# Buttons.net
KiCad netlist of a schematic drawn in Altium Designer
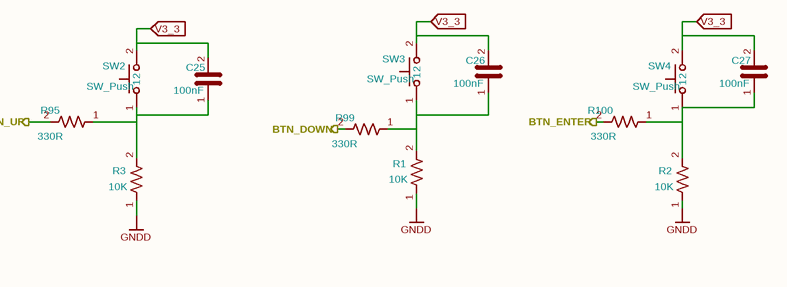
[diagram p0: Buttons.SchDoc]

(export (version "E")
  (design (tool "Eeschema 10.0.6"))
  (components
    (comp (ref "C25")
      (value "100nF")
      (footprint "C_0603_1608Metric")
      (description "X7R 100nF 50V ±10% 0603 Multilayer Ceramic")
      (fields (field (name "MP") "CC0603KRX7R9BB104") (field (name "MF") "YAGEO"))
      (libsource (lib "*") (part "C_3"))
    )
    (comp (ref "C26")
      (value "100nF")
      (footprint "C_0603_1608Metric")
      (description "X7R 100nF 50V ±10% 0603 Multilayer Ceramic")
      (fields (field (name "MP") "CC0603KRX7R9BB104") (field (name "MF") "YAGEO"))
      (libsource (lib "*") (part "C_3"))
    )
    (comp (ref "C27")
      (value "100nF")
      (footprint "C_0603_1608Metric")
      (description "X7R 100nF 50V ±10% 0603 Multilayer Ceramic")
      (fields (field (name "MP") "CC0603KRX7R9BB104") (field (name "MF") "YAGEO"))
      (libsource (lib "*") (part "C_3"))
    )
    (comp (ref "R1")
      (value "10K")
      (footprint "R_0603_1608Metric")
      (description "100mW Thick Film Resistors 75V ±100ppm/℃ ±5% 10kΩ 0603 Chip Resistor - Surface Mount ROHS")
      (fields (field (name "MP") "FRC0603J103TS") (field (name "MF") "FOJAN"))
      (libsource (lib "Device") (part "R_US"))
    )
    (comp (ref "R2")
      (value "10K")
      (footprint "R_0603_1608Metric")
      (description "100mW Thick Film Resistors 75V ±100ppm/℃ ±5% 10kΩ 0603 Chip Resistor - Surface Mount ROHS")
      (fields (field (name "MP") "FRC0603J103TS") (field (name "MF") "FOJAN"))
      (libsource (lib "Device") (part "R_US"))
    )
    (comp (ref "R3")
      (value "10K")
      (footprint "R_0603_1608Metric")
      (description "100mW Thick Film Resistors 75V ±100ppm/℃ ±5% 10kΩ 0603 Chip Resistor - Surface Mount ROHS")
      (fields (field (name "MP") "FRC0603J103TS") (field (name "MF") "FOJAN"))
      (libsource (lib "Device") (part "R_US"))
    )
    (comp (ref "R95")
      (value "330R")
      (footprint "R_0603_1608Metric")
      (description "RES 330Ω ±5% 100mW 0603")
      (fields (field (name "MP") "FRC0603J331 TS") (field (name "MF") "FOJAN"))
      (libsource (lib "Device") (part "R_US"))
    )
    (comp (ref "R99")
      (value "330R")
      (footprint "R_0603_1608Metric")
      (description "RES 330Ω ±5% 100mW 0603")
      (fields (field (name "MP") "FRC0603J331 TS") (field (name "MF") "FOJAN"))
      (libsource (lib "Device") (part "R_US"))
    )
    (comp (ref "R100")
      (value "330R")
      (footprint "R_0603_1608Metric")
      (description "RES 330Ω ±5% 100mW 0603")
      (fields (field (name "MP") "FRC0603J331 TS") (field (name "MF") "FOJAN"))
      (libsource (lib "Device") (part "R_US"))
    )
    (comp (ref "SW2")
      (value "SW_Push")
      (footprint "SW_SPST_Omron_B3FS-100xP")
      (description "Height 8mm SMD,12x12mm Tactile Switches RoHS")
      (fields (field (name "MP") "KH-12X12X8H-SMT") (field (name "MF") "kinghelm"))
      (libsource (lib "Switch") (part "SW_Push"))
    )
    (comp (ref "SW3")
      (value "SW_Push")
      (footprint "SW_SPST_Omron_B3FS-100xP")
      (description "Height 8mm SMD,12x12mm Tactile Switches RoHS")
      (fields (field (name "MP") "KH-12X12X8H-SMT") (field (name "MF") "kinghelm"))
      (libsource (lib "Switch") (part "SW_Push"))
    )
    (comp (ref "SW4")
      (value "SW_Push")
      (footprint "SW_SPST_Omron_B3FS-100xP")
      (description "Height 8mm SMD,12x12mm Tactile Switches RoHS")
      (fields (field (name "MP") "KH-12X12X8H-SMT") (field (name "MF") "kinghelm"))
      (libsource (lib "Switch") (part "SW_Push"))
    )
  )
  (nets
    (net (code "1") (name "/BTN_DOWN") (class "Default")
      (node (ref "R99") (pin "2") (pinfunction "2_2") (pintype "passive"))
    )
    (net (code "2") (name "/BTN_ENTER") (class "Default")
      (node (ref "R100") (pin "2") (pinfunction "2_2") (pintype "passive"))
    )
    (net (code "3") (name "/BTN_UP") (class "Default")
      (node (ref "R95") (pin "2") (pinfunction "2_2") (pintype "passive"))
    )
    (net (code "4") (name "/V3_3") (class "Default")
      (node (ref "C25") (pin "2") (pinfunction "2_2") (pintype "passive"))
      (node (ref "C26") (pin "2") (pinfunction "2_2") (pintype "passive"))
      (node (ref "C27") (pin "2") (pinfunction "2_2") (pintype "passive"))
      (node (ref "SW2") (pin "2") (pinfunction "2_2") (pintype "passive"))
      (node (ref "SW3") (pin "2") (pinfunction "2_2") (pintype "passive"))
      (node (ref "SW4") (pin "2") (pinfunction "2_2") (pintype "passive"))
    )
    (net (code "5") (name "GNDD") (class "Default")
      (node (ref "R1") (pin "1") (pinfunction "1_1") (pintype "passive"))
      (node (ref "R2") (pin "1") (pinfunction "1_1") (pintype "passive"))
      (node (ref "R3") (pin "1") (pinfunction "1_1") (pintype "passive"))
    )
    (net (code "6") (name "Net-(C25-Pad1)") (class "Default")
      (node (ref "C25") (pin "1") (pinfunction "1_1") (pintype "passive"))
      (node (ref "R3") (pin "2") (pinfunction "2_2") (pintype "passive"))
      (node (ref "R95") (pin "1") (pinfunction "1_1") (pintype "passive"))
      (node (ref "SW2") (pin "1") (pinfunction "1_1") (pintype "passive"))
    )
    (net (code "7") (name "Net-(C26-Pad1)") (class "Default")
      (node (ref "C26") (pin "1") (pinfunction "1_1") (pintype "passive"))
      (node (ref "R1") (pin "2") (pinfunction "2_2") (pintype "passive"))
      (node (ref "R99") (pin "1") (pinfunction "1_1") (pintype "passive"))
      (node (ref "SW3") (pin "1") (pinfunction "1_1") (pintype "passive"))
    )
    (net (code "8") (name "Net-(C27-Pad1)") (class "Default")
      (node (ref "C27") (pin "1") (pinfunction "1_1") (pintype "passive"))
      (node (ref "R100") (pin "1") (pinfunction "1_1") (pintype "passive"))
      (node (ref "R2") (pin "2") (pinfunction "2_2") (pintype "passive"))
      (node (ref "SW4") (pin "1") (pinfunction "1_1") (pintype "passive"))
    )
  )
)
